# T-Bone_Uart_Pulldown.net
KiCad netlist of a schematic drawn in EAGLE
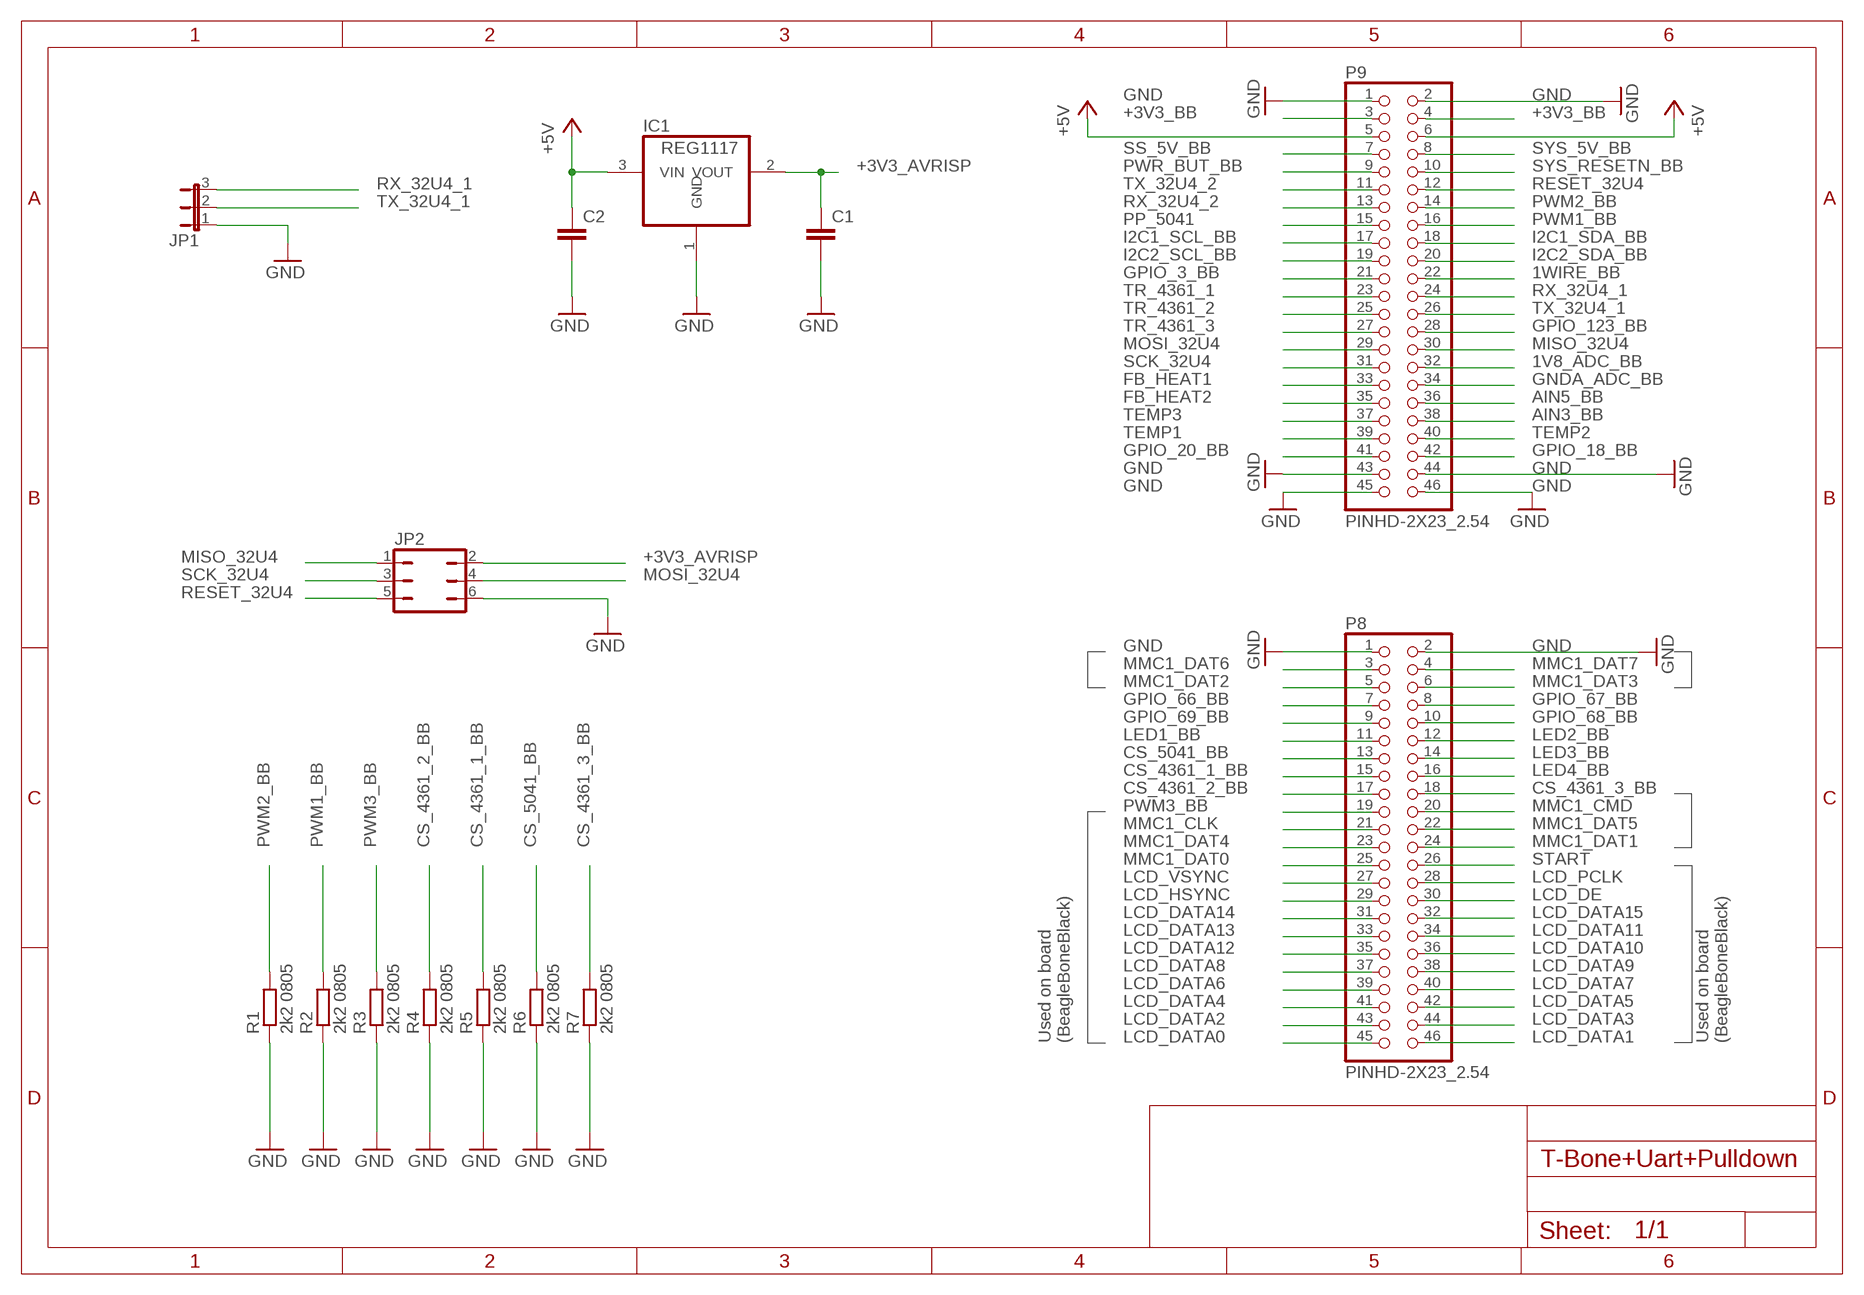
[diagram p0: schematic, sheet 1]

(export (version "E")
  (design (tool "Eeschema 10.0.6"))
  (components
    (comp (ref "C1")
      (value "C-EUC0805")
      (footprint "eagle-import:C0805")
      (libsource (lib "eagle-import") (part "C-EUC0805"))
    )
    (comp (ref "C2")
      (value "C-EUC0805")
      (footprint "eagle-import:C0805")
      (libsource (lib "eagle-import") (part "C-EUC0805"))
    )
    (comp (ref "IC1")
      (value "REG1117")
      (footprint "eagle-import:SOT223")
      (libsource (lib "eagle-import") (part "REG1117"))
    )
    (comp (ref "JP1")
      (value "JP2E")
      (footprint "eagle-import:JP2")
      (libsource (lib "eagle-import") (part "JP2E"))
    )
    (comp (ref "JP2")
      (value "JP3Q")
      (footprint "eagle-import:JP3Q")
      (libsource (lib "eagle-import") (part "JP3Q"))
    )
    (comp (ref "P8")
      (value "PINHD-2X23_2.54")
      (footprint "eagle-import:2X23")
      (libsource (lib "eagle-import") (part "PINHD-2X23_2.54"))
    )
    (comp (ref "P9")
      (value "PINHD-2X23_2.54")
      (footprint "eagle-import:2X23")
      (libsource (lib "eagle-import") (part "PINHD-2X23_2.54"))
    )
    (comp (ref "R1")
      (value "2k2 0805")
      (footprint "eagle-import:R0805")
      (libsource (lib "eagle-import") (part "R-EU_R0805"))
    )
    (comp (ref "R2")
      (value "2k2 0805")
      (footprint "eagle-import:R0805")
      (libsource (lib "eagle-import") (part "R-EU_R0805"))
    )
    (comp (ref "R3")
      (value "2k2 0805")
      (footprint "eagle-import:R0805")
      (libsource (lib "eagle-import") (part "R-EU_R0805"))
    )
    (comp (ref "R4")
      (value "2k2 0805")
      (footprint "eagle-import:R0805")
      (libsource (lib "eagle-import") (part "R-EU_R0805"))
    )
    (comp (ref "R5")
      (value "2k2 0805")
      (footprint "eagle-import:R0805")
      (libsource (lib "eagle-import") (part "R-EU_R0805"))
    )
    (comp (ref "R6")
      (value "2k2 0805")
      (footprint "eagle-import:R0805")
      (libsource (lib "eagle-import") (part "R-EU_R0805"))
    )
    (comp (ref "R7")
      (value "2k2 0805")
      (footprint "eagle-import:R0805")
      (libsource (lib "eagle-import") (part "R-EU_R0805"))
    )
  )
  (nets
    (net (code "1") (name "+5V") (class "Default")
      (node (ref "C2") (pin "1") (pinfunction "1_1") (pintype "passive"))
      (node (ref "IC1") (pin "3") (pinfunction "VIN_3") (pintype "input"))
      (node (ref "P9") (pin "5") (pinfunction "5_5") (pintype "passive"))
      (node (ref "P9") (pin "6") (pinfunction "6_6") (pintype "passive"))
    )
    (net (code "2") (name "/+3V3_AVRISP") (class "Default")
      (node (ref "C1") (pin "1") (pinfunction "1_1") (pintype "passive"))
      (node (ref "IC1") (pin "2") (pinfunction "VOUT_2") (pintype "output"))
      (node (ref "JP2") (pin "2") (pinfunction "2_2") (pintype "passive"))
    )
    (net (code "3") (name "/+3V3_BB") (class "Default")
      (node (ref "P9") (pin "3") (pinfunction "3_3") (pintype "passive"))
      (node (ref "P9") (pin "4") (pinfunction "4_4") (pintype "passive"))
    )
    (net (code "4") (name "/1V8_ADC_BB") (class "Default")
      (node (ref "P9") (pin "32") (pinfunction "32_32") (pintype "passive"))
    )
    (net (code "5") (name "/1WIRE_BB") (class "Default")
      (node (ref "P9") (pin "22") (pinfunction "22_22") (pintype "passive"))
    )
    (net (code "6") (name "/AIN3_BB") (class "Default")
      (node (ref "P9") (pin "38") (pinfunction "38_38") (pintype "passive"))
    )
    (net (code "7") (name "/AIN5_BB") (class "Default")
      (node (ref "P9") (pin "36") (pinfunction "36_36") (pintype "passive"))
    )
    (net (code "8") (name "/CS_4361_1_BB") (class "Default")
      (node (ref "P8") (pin "15") (pinfunction "15_15") (pintype "passive"))
      (node (ref "R5") (pin "2") (pinfunction "2_2") (pintype "passive"))
    )
    (net (code "9") (name "/CS_4361_2_BB") (class "Default")
      (node (ref "P8") (pin "17") (pinfunction "17_17") (pintype "passive"))
      (node (ref "R4") (pin "2") (pinfunction "2_2") (pintype "passive"))
    )
    (net (code "10") (name "/CS_4361_3_BB") (class "Default")
      (node (ref "P8") (pin "18") (pinfunction "18_18") (pintype "passive"))
      (node (ref "R7") (pin "2") (pinfunction "2_2") (pintype "passive"))
    )
    (net (code "11") (name "/CS_5041_BB") (class "Default")
      (node (ref "P8") (pin "13") (pinfunction "13_13") (pintype "passive"))
      (node (ref "R6") (pin "2") (pinfunction "2_2") (pintype "passive"))
    )
    (net (code "12") (name "/FB_HEAT1") (class "Default")
      (node (ref "P9") (pin "33") (pinfunction "33_33") (pintype "passive"))
    )
    (net (code "13") (name "/FB_HEAT2") (class "Default")
      (node (ref "P9") (pin "35") (pinfunction "35_35") (pintype "passive"))
    )
    (net (code "14") (name "/GNDA_ADC_BB") (class "Default")
      (node (ref "P9") (pin "34") (pinfunction "34_34") (pintype "passive"))
    )
    (net (code "15") (name "/GPIO_3_BB") (class "Default")
      (node (ref "P9") (pin "21") (pinfunction "21_21") (pintype "passive"))
    )
    (net (code "16") (name "/GPIO_18_BB") (class "Default")
      (node (ref "P9") (pin "42") (pinfunction "42_42") (pintype "passive"))
    )
    (net (code "17") (name "/GPIO_20_BB") (class "Default")
      (node (ref "P9") (pin "41") (pinfunction "41_41") (pintype "passive"))
    )
    (net (code "18") (name "/GPIO_66_BB") (class "Default")
      (node (ref "P8") (pin "7") (pinfunction "7_7") (pintype "passive"))
    )
    (net (code "19") (name "/GPIO_67_BB") (class "Default")
      (node (ref "P8") (pin "8") (pinfunction "8_8") (pintype "passive"))
    )
    (net (code "20") (name "/GPIO_68_BB") (class "Default")
      (node (ref "P8") (pin "10") (pinfunction "10_10") (pintype "passive"))
    )
    (net (code "21") (name "/GPIO_69_BB") (class "Default")
      (node (ref "P8") (pin "9") (pinfunction "9_9") (pintype "passive"))
    )
    (net (code "22") (name "/GPIO_123_BB") (class "Default")
      (node (ref "P9") (pin "28") (pinfunction "28_28") (pintype "passive"))
    )
    (net (code "23") (name "/I2C1_SCL_BB") (class "Default")
      (node (ref "P9") (pin "17") (pinfunction "17_17") (pintype "passive"))
    )
    (net (code "24") (name "/I2C1_SDA_BB") (class "Default")
      (node (ref "P9") (pin "18") (pinfunction "18_18") (pintype "passive"))
    )
    (net (code "25") (name "/I2C2_SCL_BB") (class "Default")
      (node (ref "P9") (pin "19") (pinfunction "19_19") (pintype "passive"))
    )
    (net (code "26") (name "/I2C2_SDA_BB") (class "Default")
      (node (ref "P9") (pin "20") (pinfunction "20_20") (pintype "passive"))
    )
    (net (code "27") (name "/LCD_DATA0") (class "Default")
      (node (ref "P8") (pin "45") (pinfunction "45_45") (pintype "passive"))
    )
    (net (code "28") (name "/LCD_DATA1") (class "Default")
      (node (ref "P8") (pin "46") (pinfunction "46_46") (pintype "passive"))
    )
    (net (code "29") (name "/LCD_DATA2") (class "Default")
      (node (ref "P8") (pin "43") (pinfunction "43_43") (pintype "passive"))
    )
    (net (code "30") (name "/LCD_DATA3") (class "Default")
      (node (ref "P8") (pin "44") (pinfunction "44_44") (pintype "passive"))
    )
    (net (code "31") (name "/LCD_DATA4") (class "Default")
      (node (ref "P8") (pin "41") (pinfunction "41_41") (pintype "passive"))
    )
    (net (code "32") (name "/LCD_DATA5") (class "Default")
      (node (ref "P8") (pin "42") (pinfunction "42_42") (pintype "passive"))
    )
    (net (code "33") (name "/LCD_DATA6") (class "Default")
      (node (ref "P8") (pin "39") (pinfunction "39_39") (pintype "passive"))
    )
    (net (code "34") (name "/LCD_DATA7") (class "Default")
      (node (ref "P8") (pin "40") (pinfunction "40_40") (pintype "passive"))
    )
    (net (code "35") (name "/LCD_DATA8") (class "Default")
      (node (ref "P8") (pin "37") (pinfunction "37_37") (pintype "passive"))
    )
    (net (code "36") (name "/LCD_DATA9") (class "Default")
      (node (ref "P8") (pin "38") (pinfunction "38_38") (pintype "passive"))
    )
    (net (code "37") (name "/LCD_DATA10") (class "Default")
      (node (ref "P8") (pin "36") (pinfunction "36_36") (pintype "passive"))
    )
    (net (code "38") (name "/LCD_DATA11") (class "Default")
      (node (ref "P8") (pin "34") (pinfunction "34_34") (pintype "passive"))
    )
    (net (code "39") (name "/LCD_DATA12") (class "Default")
      (node (ref "P8") (pin "35") (pinfunction "35_35") (pintype "passive"))
    )
    (net (code "40") (name "/LCD_DATA13") (class "Default")
      (node (ref "P8") (pin "33") (pinfunction "33_33") (pintype "passive"))
    )
    (net (code "41") (name "/LCD_DATA14") (class "Default")
      (node (ref "P8") (pin "31") (pinfunction "31_31") (pintype "passive"))
    )
    (net (code "42") (name "/LCD_DATA15") (class "Default")
      (node (ref "P8") (pin "32") (pinfunction "32_32") (pintype "passive"))
    )
    (net (code "43") (name "/LCD_DE") (class "Default")
      (node (ref "P8") (pin "30") (pinfunction "30_30") (pintype "passive"))
    )
    (net (code "44") (name "/LCD_HSYNC") (class "Default")
      (node (ref "P8") (pin "29") (pinfunction "29_29") (pintype "passive"))
    )
    (net (code "45") (name "/LCD_PCLK") (class "Default")
      (node (ref "P8") (pin "28") (pinfunction "28_28") (pintype "passive"))
    )
    (net (code "46") (name "/LCD_VSYNC") (class "Default")
      (node (ref "P8") (pin "27") (pinfunction "27_27") (pintype "passive"))
    )
    (net (code "47") (name "/LED1_BB") (class "Default")
      (node (ref "P8") (pin "11") (pinfunction "11_11") (pintype "passive"))
    )
    (net (code "48") (name "/LED2_BB") (class "Default")
      (node (ref "P8") (pin "12") (pinfunction "12_12") (pintype "passive"))
    )
    (net (code "49") (name "/LED3_BB") (class "Default")
      (node (ref "P8") (pin "14") (pinfunction "14_14") (pintype "passive"))
    )
    (net (code "50") (name "/LED4_BB") (class "Default")
      (node (ref "P8") (pin "16") (pinfunction "16_16") (pintype "passive"))
    )
    (net (code "51") (name "/MISO_32U4") (class "Default")
      (node (ref "JP2") (pin "1") (pinfunction "1_1") (pintype "passive"))
      (node (ref "P9") (pin "30") (pinfunction "30_30") (pintype "passive"))
    )
    (net (code "52") (name "/MMC1_CLK") (class "Default")
      (node (ref "P8") (pin "21") (pinfunction "21_21") (pintype "passive"))
    )
    (net (code "53") (name "/MMC1_CMD") (class "Default")
      (node (ref "P8") (pin "20") (pinfunction "20_20") (pintype "passive"))
    )
    (net (code "54") (name "/MMC1_DAT0") (class "Default")
      (node (ref "P8") (pin "25") (pinfunction "25_25") (pintype "passive"))
    )
    (net (code "55") (name "/MMC1_DAT1") (class "Default")
      (node (ref "P8") (pin "24") (pinfunction "24_24") (pintype "passive"))
    )
    (net (code "56") (name "/MMC1_DAT2") (class "Default")
      (node (ref "P8") (pin "5") (pinfunction "5_5") (pintype "passive"))
    )
    (net (code "57") (name "/MMC1_DAT3") (class "Default")
      (node (ref "P8") (pin "6") (pinfunction "6_6") (pintype "passive"))
    )
    (net (code "58") (name "/MMC1_DAT4") (class "Default")
      (node (ref "P8") (pin "23") (pinfunction "23_23") (pintype "passive"))
    )
    (net (code "59") (name "/MMC1_DAT5") (class "Default")
      (node (ref "P8") (pin "22") (pinfunction "22_22") (pintype "passive"))
    )
    (net (code "60") (name "/MMC1_DAT6") (class "Default")
      (node (ref "P8") (pin "3") (pinfunction "3_3") (pintype "passive"))
    )
    (net (code "61") (name "/MMC1_DAT7") (class "Default")
      (node (ref "P8") (pin "4") (pinfunction "4_4") (pintype "passive"))
    )
    (net (code "62") (name "/MOSI_32U4") (class "Default")
      (node (ref "JP2") (pin "4") (pinfunction "4_4") (pintype "passive"))
      (node (ref "P9") (pin "29") (pinfunction "29_29") (pintype "passive"))
    )
    (net (code "63") (name "/PP_5041") (class "Default")
      (node (ref "P9") (pin "15") (pinfunction "15_15") (pintype "passive"))
    )
    (net (code "64") (name "/PWM1_BB") (class "Default")
      (node (ref "P9") (pin "16") (pinfunction "16_16") (pintype "passive"))
      (node (ref "R2") (pin "2") (pinfunction "2_2") (pintype "passive"))
    )
    (net (code "65") (name "/PWM2_BB") (class "Default")
      (node (ref "P9") (pin "14") (pinfunction "14_14") (pintype "passive"))
      (node (ref "R1") (pin "2") (pinfunction "2_2") (pintype "passive"))
    )
    (net (code "66") (name "/PWM3_BB") (class "Default")
      (node (ref "P8") (pin "19") (pinfunction "19_19") (pintype "passive"))
      (node (ref "R3") (pin "2") (pinfunction "2_2") (pintype "passive"))
    )
    (net (code "67") (name "/PWR_BUT_BB") (class "Default")
      (node (ref "P9") (pin "9") (pinfunction "9_9") (pintype "passive"))
    )
    (net (code "68") (name "/RESET_32U4") (class "Default")
      (node (ref "JP2") (pin "5") (pinfunction "5_5") (pintype "passive"))
      (node (ref "P9") (pin "12") (pinfunction "12_12") (pintype "passive"))
    )
    (net (code "69") (name "/RX_32U4_1") (class "Default")
      (node (ref "JP1") (pin "3") (pinfunction "3_3") (pintype "passive"))
      (node (ref "P9") (pin "24") (pinfunction "24_24") (pintype "passive"))
    )
    (net (code "70") (name "/RX_32U4_2") (class "Default")
      (node (ref "P9") (pin "13") (pinfunction "13_13") (pintype "passive"))
    )
    (net (code "71") (name "/SCK_32U4") (class "Default")
      (node (ref "JP2") (pin "3") (pinfunction "3_3") (pintype "passive"))
      (node (ref "P9") (pin "31") (pinfunction "31_31") (pintype "passive"))
    )
    (net (code "72") (name "/SS_5V_BB") (class "Default")
      (node (ref "P9") (pin "7") (pinfunction "7_7") (pintype "passive"))
    )
    (net (code "73") (name "/START") (class "Default")
      (node (ref "P8") (pin "26") (pinfunction "26_26") (pintype "passive"))
    )
    (net (code "74") (name "/SYS_5V_BB") (class "Default")
      (node (ref "P9") (pin "8") (pinfunction "8_8") (pintype "passive"))
    )
    (net (code "75") (name "/SYS_RESETN_BB") (class "Default")
      (node (ref "P9") (pin "10") (pinfunction "10_10") (pintype "passive"))
    )
    (net (code "76") (name "/TEMP1") (class "Default")
      (node (ref "P9") (pin "39") (pinfunction "39_39") (pintype "passive"))
    )
    (net (code "77") (name "/TEMP2") (class "Default")
      (node (ref "P9") (pin "40") (pinfunction "40_40") (pintype "passive"))
    )
    (net (code "78") (name "/TEMP3") (class "Default")
      (node (ref "P9") (pin "37") (pinfunction "37_37") (pintype "passive"))
    )
    (net (code "79") (name "/TR_4361_1") (class "Default")
      (node (ref "P9") (pin "23") (pinfunction "23_23") (pintype "passive"))
    )
    (net (code "80") (name "/TR_4361_2") (class "Default")
      (node (ref "P9") (pin "25") (pinfunction "25_25") (pintype "passive"))
    )
    (net (code "81") (name "/TR_4361_3") (class "Default")
      (node (ref "P9") (pin "27") (pinfunction "27_27") (pintype "passive"))
    )
    (net (code "82") (name "/TX_32U4_1") (class "Default")
      (node (ref "JP1") (pin "2") (pinfunction "2_2") (pintype "passive"))
      (node (ref "P9") (pin "26") (pinfunction "26_26") (pintype "passive"))
    )
    (net (code "83") (name "/TX_32U4_2") (class "Default")
      (node (ref "P9") (pin "11") (pinfunction "11_11") (pintype "passive"))
    )
    (net (code "84") (name "GND") (class "Default")
      (node (ref "C1") (pin "2") (pinfunction "2_2") (pintype "passive"))
      (node (ref "C2") (pin "2") (pinfunction "2_2") (pintype "passive"))
      (node (ref "IC1") (pin "1") (pinfunction "GND_1") (pintype "power_in"))
      (node (ref "JP1") (pin "1") (pinfunction "1_1") (pintype "passive"))
      (node (ref "JP2") (pin "6") (pinfunction "6_6") (pintype "passive"))
      (node (ref "P8") (pin "1") (pinfunction "1_1") (pintype "passive"))
      (node (ref "P8") (pin "2") (pinfunction "2_2") (pintype "passive"))
      (node (ref "P9") (pin "1") (pinfunction "1_1") (pintype "passive"))
      (node (ref "P9") (pin "2") (pinfunction "2_2") (pintype "passive"))
      (node (ref "P9") (pin "43") (pinfunction "43_43") (pintype "passive"))
      (node (ref "P9") (pin "44") (pinfunction "44_44") (pintype "passive"))
      (node (ref "P9") (pin "45") (pinfunction "45_45") (pintype "passive"))
      (node (ref "P9") (pin "46") (pinfunction "46_46") (pintype "passive"))
      (node (ref "R1") (pin "1") (pinfunction "1_1") (pintype "passive"))
      (node (ref "R2") (pin "1") (pinfunction "1_1") (pintype "passive"))
      (node (ref "R3") (pin "1") (pinfunction "1_1") (pintype "passive"))
      (node (ref "R4") (pin "1") (pinfunction "1_1") (pintype "passive"))
      (node (ref "R5") (pin "1") (pinfunction "1_1") (pintype "passive"))
      (node (ref "R6") (pin "1") (pinfunction "1_1") (pintype "passive"))
      (node (ref "R7") (pin "1") (pinfunction "1_1") (pintype "passive"))
    )
  )
)
